# radio_fm_cd2003_tda2822.net
KiCad netlist of a schematic drawn in EAGLE
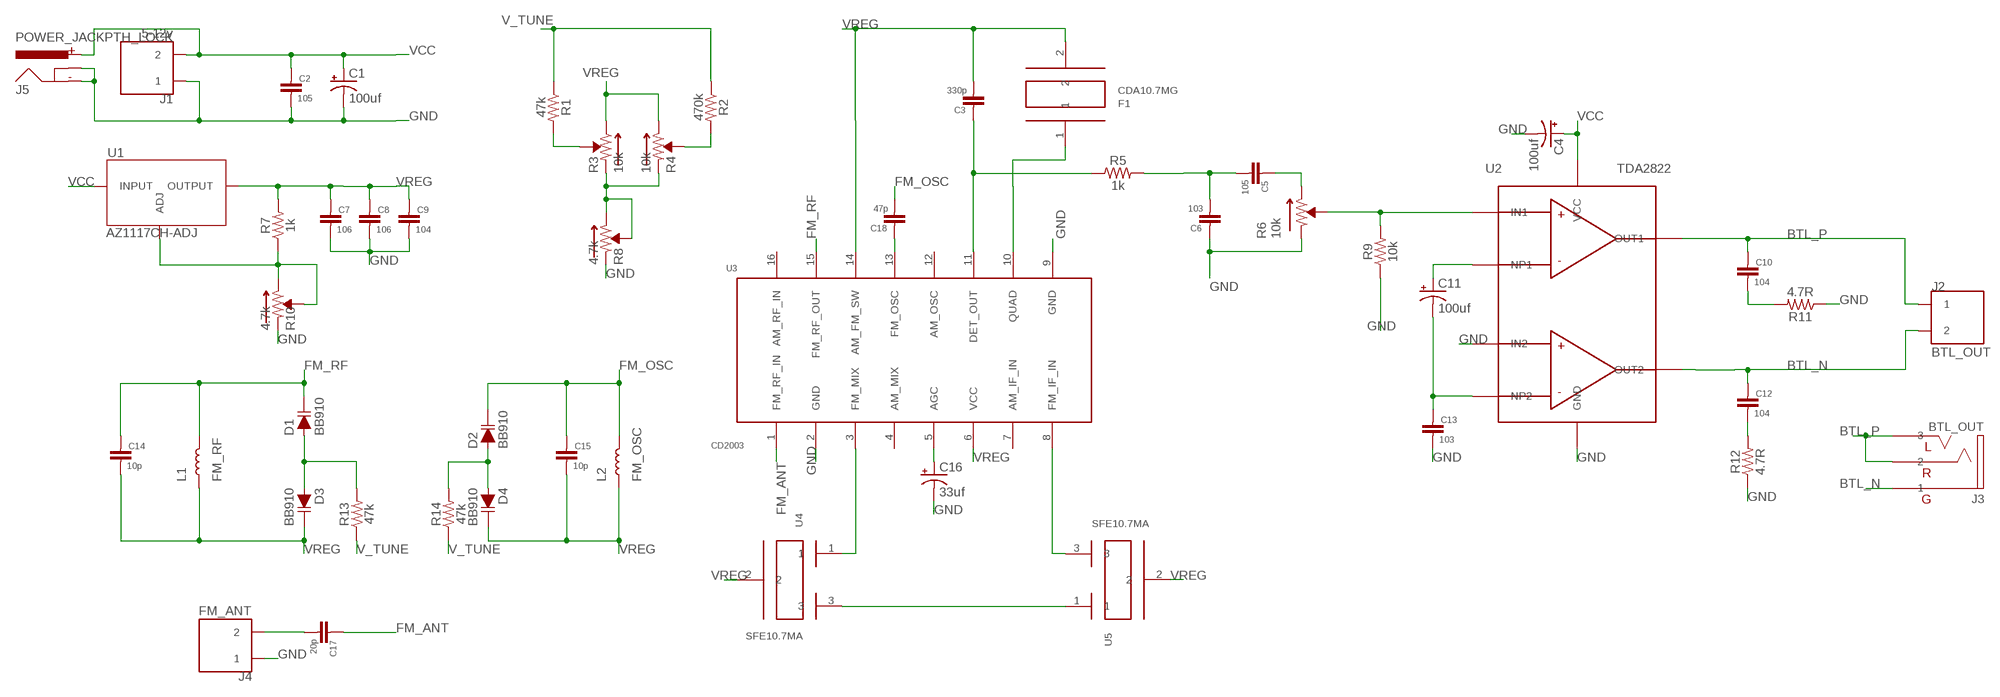
[diagram p0: schematic, sheet 1]

(export (version "E")
  (design (tool "Eeschema 10.0.6"))
  (components
    (comp (ref "C1")
      (value "100uf")
      (footprint "eagle-import:CAP_2.5MM")
      (libsource (lib "eagle-import") (part "CAP"))
    )
    (comp (ref "C2")
      (value "105")
      (footprint "eagle-import:C0603")
      (libsource (lib "eagle-import") (part "CAP_SMDC0603"))
    )
    (comp (ref "C3")
      (value "330p")
      (footprint "eagle-import:C0603")
      (libsource (lib "eagle-import") (part "CAP_SMDC0603"))
    )
    (comp (ref "C4")
      (value "100uf")
      (footprint "eagle-import:CAP_2.5MM")
      (libsource (lib "eagle-import") (part "CAP"))
    )
    (comp (ref "C5")
      (value "105")
      (footprint "eagle-import:C0603")
      (libsource (lib "eagle-import") (part "CAP_SMDC0603"))
    )
    (comp (ref "C6")
      (value "103")
      (footprint "eagle-import:C0603")
      (libsource (lib "eagle-import") (part "CAP_SMDC0603"))
    )
    (comp (ref "C7")
      (value "106")
      (footprint "eagle-import:C0603")
      (libsource (lib "eagle-import") (part "CAP_SMDC0603"))
    )
    (comp (ref "C8")
      (value "106")
      (footprint "eagle-import:C0603")
      (libsource (lib "eagle-import") (part "CAP_SMDC0603"))
    )
    (comp (ref "C9")
      (value "104")
      (footprint "eagle-import:C0603")
      (libsource (lib "eagle-import") (part "CAP_SMDC0603"))
    )
    (comp (ref "C10")
      (value "104")
      (footprint "eagle-import:C0603")
      (libsource (lib "eagle-import") (part "CAP_SMDC0603"))
    )
    (comp (ref "C11")
      (value "100uf")
      (footprint "eagle-import:CAP_2.5MM")
      (libsource (lib "eagle-import") (part "CAP"))
    )
    (comp (ref "C12")
      (value "104")
      (footprint "eagle-import:C0603")
      (libsource (lib "eagle-import") (part "CAP_SMDC0603"))
    )
    (comp (ref "C13")
      (value "103")
      (footprint "eagle-import:C0603")
      (libsource (lib "eagle-import") (part "CAP_SMDC0603"))
    )
    (comp (ref "C14")
      (value "10p")
      (footprint "eagle-import:C0603")
      (libsource (lib "eagle-import") (part "CAP_SMDC0603"))
    )
    (comp (ref "C15")
      (value "10p")
      (footprint "eagle-import:C0603")
      (libsource (lib "eagle-import") (part "CAP_SMDC0603"))
    )
    (comp (ref "C16")
      (value "33uf")
      (footprint "eagle-import:CAP_2MM")
      (libsource (lib "eagle-import") (part "CAP2MM"))
    )
    (comp (ref "C17")
      (value "20p")
      (footprint "eagle-import:C0603")
      (libsource (lib "eagle-import") (part "CAP_SMDC0603"))
    )
    (comp (ref "C18")
      (value "47p")
      (footprint "eagle-import:C0603")
      (libsource (lib "eagle-import") (part "CAP_SMDC0603"))
    )
    (comp (ref "D1")
      (value "BB910")
      (footprint "eagle-import:TO-92S")
      (libsource (lib "eagle-import") (part "VARIODE-TO92S"))
    )
    (comp (ref "D2")
      (value "BB910")
      (footprint "eagle-import:TO-92S")
      (libsource (lib "eagle-import") (part "VARIODE-TO92S"))
    )
    (comp (ref "D3")
      (value "BB910")
      (footprint "eagle-import:TO-92S")
      (libsource (lib "eagle-import") (part "VARIODE-TO92S"))
    )
    (comp (ref "D4")
      (value "BB910")
      (footprint "eagle-import:TO-92S")
      (libsource (lib "eagle-import") (part "VARIODE-TO92S"))
    )
    (comp (ref "F1")
      (value "CDA10.7MG")
      (footprint "eagle-import:CDA10.7MG")
      (libsource (lib "eagle-import") (part "CDA10.7MG"))
    )
    (comp (ref "J1")
      (value "5-12v")
      (footprint "eagle-import:2P_2.54MM")
      (libsource (lib "eagle-import") (part "2P"))
    )
    (comp (ref "J2")
      (value "BTL_OUT")
      (footprint "eagle-import:2P_5.08MM")
      (libsource (lib "eagle-import") (part "2P5.0"))
    )
    (comp (ref "J3")
      (value "BTL_OUT")
      (footprint "eagle-import:3.5MM")
      (libsource (lib "eagle-import") (part "3.5MM_PHONE"))
    )
    (comp (ref "J4")
      (value "FM_ANT")
      (footprint "eagle-import:2P_2.54MM")
      (libsource (lib "eagle-import") (part "2P"))
    )
    (comp (ref "J5")
      (value "POWER_JACKPTH_LOCK")
      (footprint "eagle-import:POWER_JACK_PTH_LOCK")
      (libsource (lib "eagle-import") (part "POWER_JACKPTH_LOCK"))
    )
    (comp (ref "L1")
      (value "FM_RF")
      (footprint "eagle-import:VLU0810")
      (libsource (lib "eagle-import") (part "INDUCTOR_PTH"))
    )
    (comp (ref "L2")
      (value "FM_OSC")
      (footprint "eagle-import:VLU0810")
      (libsource (lib "eagle-import") (part "INDUCTOR_PTH"))
    )
    (comp (ref "R1")
      (value "47k")
      (footprint "eagle-import:R0603")
      (libsource (lib "eagle-import") (part "RESISTOR_SMDR0603"))
    )
    (comp (ref "R2")
      (value "470k")
      (footprint "eagle-import:R0603")
      (libsource (lib "eagle-import") (part "RESISTOR_SMDR0603"))
    )
    (comp (ref "R3")
      (value "10k")
      (footprint "eagle-import:3362P")
      (libsource (lib "eagle-import") (part "RES_ADJ"))
    )
    (comp (ref "R4")
      (value "10k")
      (footprint "eagle-import:3362P")
      (libsource (lib "eagle-import") (part "RES_ADJ"))
    )
    (comp (ref "R5")
      (value "1k")
      (footprint "eagle-import:R0603")
      (libsource (lib "eagle-import") (part "RESISTOR_SMDR0603"))
    )
    (comp (ref "R6")
      (value "10k")
      (footprint "eagle-import:3362P")
      (libsource (lib "eagle-import") (part "RES_ADJ"))
    )
    (comp (ref "R7")
      (value "1k")
      (footprint "eagle-import:R0603")
      (libsource (lib "eagle-import") (part "RESISTOR_SMDR0603"))
    )
    (comp (ref "R8")
      (value "4.7k")
      (footprint "eagle-import:3362P")
      (libsource (lib "eagle-import") (part "RES_ADJ"))
    )
    (comp (ref "R9")
      (value "10k")
      (footprint "eagle-import:R0603")
      (libsource (lib "eagle-import") (part "RESISTOR_SMDR0603"))
    )
    (comp (ref "R10")
      (value "4.7k")
      (footprint "eagle-import:3362P")
      (libsource (lib "eagle-import") (part "RES_ADJ"))
    )
    (comp (ref "R11")
      (value "4.7R")
      (footprint "eagle-import:R0603")
      (libsource (lib "eagle-import") (part "RESISTOR_SMDR0603"))
    )
    (comp (ref "R12")
      (value "4.7R")
      (footprint "eagle-import:R0603")
      (libsource (lib "eagle-import") (part "RESISTOR_SMDR0603"))
    )
    (comp (ref "R13")
      (value "47k")
      (footprint "eagle-import:R0603")
      (libsource (lib "eagle-import") (part "RESISTOR_SMDR0603"))
    )
    (comp (ref "R14")
      (value "47k")
      (footprint "eagle-import:R0603")
      (libsource (lib "eagle-import") (part "RESISTOR_SMDR0603"))
    )
    (comp (ref "U1")
      (value "AZ1117CH-ADJ")
      (footprint "eagle-import:SOT-223")
      (libsource (lib "eagle-import") (part "AZ1117CH-ADJ"))
    )
    (comp (ref "U2")
      (value "TDA2822")
      (footprint "eagle-import:DIP8")
      (libsource (lib "eagle-import") (part "TDA2822-DIP8"))
    )
    (comp (ref "U3")
      (value "CD2003")
      (footprint "eagle-import:DIP16")
      (libsource (lib "eagle-import") (part "TA2003"))
    )
    (comp (ref "U4")
      (value "SFE10.7MA")
      (footprint "eagle-import:SFE10.7MA")
      (libsource (lib "eagle-import") (part "SFE10.7MA"))
    )
    (comp (ref "U5")
      (value "SFE10.7MA")
      (footprint "eagle-import:SFE10.7MA")
      (libsource (lib "eagle-import") (part "SFE10.7MA"))
    )
  )
  (nets
    (net (code "1") (name "/BTL_N") (class "Default")
      (node (ref "C12") (pin "1") (pinfunction "1_1") (pintype "passive"))
      (node (ref "J2") (pin "N") (pinfunction "2_N") (pintype "bidirectional"))
      (node (ref "J3") (pin "P$1") (pinfunction "1_P$1") (pintype "bidirectional"))
      (node (ref "U2") (pin "P$3") (pinfunction "OUT2_P$3") (pintype "bidirectional"))
    )
    (net (code "2") (name "/BTL_P") (class "Default")
      (node (ref "C10") (pin "1") (pinfunction "1_1") (pintype "passive"))
      (node (ref "J2") (pin "L") (pinfunction "1_L") (pintype "bidirectional"))
      (node (ref "J3") (pin "P$2") (pinfunction "2_P$2") (pintype "bidirectional"))
      (node (ref "J3") (pin "P$3") (pinfunction "3_P$3") (pintype "bidirectional"))
      (node (ref "U2") (pin "P$1") (pinfunction "OUT1_P$1") (pintype "bidirectional"))
    )
    (net (code "3") (name "/FM_ANT") (class "Default")
      (node (ref "C17") (pin "1") (pinfunction "1_1") (pintype "passive"))
      (node (ref "U3") (pin "1") (pinfunction "FM_RF_IN_1") (pintype "bidirectional"))
    )
    (net (code "4") (name "/FM_OSC") (class "Default")
      (node (ref "C15") (pin "1") (pinfunction "1_1") (pintype "passive"))
      (node (ref "C18") (pin "2") (pinfunction "2_2") (pintype "passive"))
      (node (ref "D2") (pin "2") (pinfunction "C_2") (pintype "passive"))
      (node (ref "L2") (pin "-") (pinfunction "2_-") (pintype "passive"))
    )
    (net (code "5") (name "/FM_RF") (class "Default")
      (node (ref "C14") (pin "1") (pinfunction "1_1") (pintype "passive"))
      (node (ref "D1") (pin "2") (pinfunction "C_2") (pintype "passive"))
      (node (ref "L1") (pin "-") (pinfunction "2_-") (pintype "passive"))
      (node (ref "U3") (pin "15") (pinfunction "FM_RF_OUT_15") (pintype "bidirectional"))
    )
    (net (code "6") (name "/GND") (class "Default")
      (node (ref "C1") (pin "-") (pinfunction "-_-") (pintype "passive"))
      (node (ref "C13") (pin "2") (pinfunction "2_2") (pintype "passive"))
      (node (ref "C16") (pin "-") (pinfunction "-_-") (pintype "passive"))
      (node (ref "C2") (pin "2") (pinfunction "2_2") (pintype "passive"))
      (node (ref "C4") (pin "-") (pinfunction "-_-") (pintype "passive"))
      (node (ref "C6") (pin "1") (pinfunction "1_1") (pintype "passive"))
      (node (ref "C7") (pin "2") (pinfunction "2_2") (pintype "passive"))
      (node (ref "C8") (pin "2") (pinfunction "2_2") (pintype "passive"))
      (node (ref "C9") (pin "2") (pinfunction "2_2") (pintype "passive"))
      (node (ref "J1") (pin "1") (pinfunction "1_1") (pintype "bidirectional"))
      (node (ref "J4") (pin "1") (pinfunction "1_1") (pintype "bidirectional"))
      (node (ref "J5") (pin "GND") (pinfunction "GND_GND") (pintype "bidirectional"))
      (node (ref "J5") (pin "GNDBREAK") (pinfunction "GNDBREAK_GNDBREAK") (pintype "bidirectional"))
      (node (ref "R10") (pin "P$1") (pinfunction "1_P$1") (pintype "passive"))
      (node (ref "R11") (pin "1") (pinfunction "1_1") (pintype "passive"))
      (node (ref "R12") (pin "1") (pinfunction "1_1") (pintype "passive"))
      (node (ref "R6") (pin "P$1") (pinfunction "1_P$1") (pintype "passive"))
      (node (ref "R8") (pin "P$1") (pinfunction "1_P$1") (pintype "passive"))
      (node (ref "R9") (pin "1") (pinfunction "1_1") (pintype "passive"))
      (node (ref "U2") (pin "P$4") (pinfunction "GND_P$4") (pintype "bidirectional"))
      (node (ref "U2") (pin "P$6") (pinfunction "IN2_P$6") (pintype "bidirectional"))
      (node (ref "U3") (pin "2") (pinfunction "GND_2") (pintype "bidirectional"))
      (node (ref "U3") (pin "9") (pinfunction "GND_9") (pintype "bidirectional"))
    )
    (net (code "7") (name "/VCC") (class "Default")
      (node (ref "C1") (pin "+") (pinfunction "+_+") (pintype "passive"))
      (node (ref "C2") (pin "1") (pinfunction "1_1") (pintype "passive"))
      (node (ref "C4") (pin "+") (pinfunction "+_+") (pintype "passive"))
      (node (ref "J1") (pin "2") (pinfunction "2_2") (pintype "bidirectional"))
      (node (ref "J5") (pin "PWR") (pinfunction "PWR_PWR") (pintype "bidirectional"))
      (node (ref "U1") (pin "3") (pinfunction "INPUT_3") (pintype "bidirectional"))
      (node (ref "U2") (pin "P$2") (pinfunction "VCC_P$2") (pintype "bidirectional"))
    )
    (net (code "8") (name "/VREG") (class "Default")
      (node (ref "C14") (pin "2") (pinfunction "2_2") (pintype "passive"))
      (node (ref "C15") (pin "2") (pinfunction "2_2") (pintype "passive"))
      (node (ref "C3") (pin "2") (pinfunction "2_2") (pintype "passive"))
      (node (ref "C7") (pin "1") (pinfunction "1_1") (pintype "passive"))
      (node (ref "C8") (pin "1") (pinfunction "1_1") (pintype "passive"))
      (node (ref "C9") (pin "1") (pinfunction "1_1") (pintype "passive"))
      (node (ref "D3") (pin "2") (pinfunction "C_2") (pintype "passive"))
      (node (ref "D4") (pin "2") (pinfunction "C_2") (pintype "passive"))
      (node (ref "F1") (pin "2") (pinfunction "2_2") (pintype "bidirectional"))
      (node (ref "L1") (pin "+") (pinfunction "1_+") (pintype "passive"))
      (node (ref "L2") (pin "+") (pinfunction "1_+") (pintype "passive"))
      (node (ref "R3") (pin "P$3") (pinfunction "3_P$3") (pintype "passive"))
      (node (ref "R4") (pin "P$3") (pinfunction "3_P$3") (pintype "passive"))
      (node (ref "R7") (pin "2") (pinfunction "2_2") (pintype "passive"))
      (node (ref "U1") (pin "2") (pinfunction "OUTPUT_2") (pintype "bidirectional"))
      (node (ref "U3") (pin "14") (pinfunction "AM_FM_SW_14") (pintype "bidirectional"))
      (node (ref "U3") (pin "6") (pinfunction "VCC_6") (pintype "bidirectional"))
      (node (ref "U4") (pin "2") (pinfunction "2_2") (pintype "bidirectional"))
      (node (ref "U5") (pin "2") (pinfunction "2_2") (pintype "bidirectional"))
    )
    (net (code "9") (name "/V_TUNE") (class "Default")
      (node (ref "R1") (pin "1") (pinfunction "1_1") (pintype "passive"))
      (node (ref "R13") (pin "1") (pinfunction "1_1") (pintype "passive"))
      (node (ref "R14") (pin "1") (pinfunction "1_1") (pintype "passive"))
      (node (ref "R2") (pin "1") (pinfunction "1_1") (pintype "passive"))
    )
    (net (code "10") (name "Net-(C5-Pad2)") (class "Default")
      (node (ref "C5") (pin "2") (pinfunction "2_2") (pintype "passive"))
      (node (ref "C6") (pin "2") (pinfunction "2_2") (pintype "passive"))
      (node (ref "R5") (pin "2") (pinfunction "2_2") (pintype "passive"))
    )
    (net (code "11") (name "Net-(C10-Pad2)") (class "Default")
      (node (ref "C10") (pin "2") (pinfunction "2_2") (pintype "passive"))
      (node (ref "R11") (pin "2") (pinfunction "2_2") (pintype "passive"))
    )
    (net (code "12") (name "Net-(C12-Pad2)") (class "Default")
      (node (ref "C12") (pin "2") (pinfunction "2_2") (pintype "passive"))
      (node (ref "R12") (pin "2") (pinfunction "2_2") (pintype "passive"))
    )
    (net (code "13") (name "Net-(C17-Pad2)") (class "Default")
      (node (ref "C17") (pin "2") (pinfunction "2_2") (pintype "passive"))
      (node (ref "J4") (pin "2") (pinfunction "2_2") (pintype "bidirectional"))
    )
    (net (code "14") (name "Net-(D1-A)") (class "Default")
      (node (ref "D1") (pin "1") (pinfunction "A_1") (pintype "passive"))
      (node (ref "D3") (pin "1") (pinfunction "A_1") (pintype "passive"))
      (node (ref "R13") (pin "2") (pinfunction "2_2") (pintype "passive"))
    )
    (net (code "15") (name "Net-(D2-A)") (class "Default")
      (node (ref "D2") (pin "1") (pinfunction "A_1") (pintype "passive"))
      (node (ref "D4") (pin "1") (pinfunction "A_1") (pintype "passive"))
      (node (ref "R14") (pin "2") (pinfunction "2_2") (pintype "passive"))
    )
    (net (code "16") (name "Net-(R3-1)") (class "Default")
      (node (ref "R3") (pin "P$1") (pinfunction "1_P$1") (pintype "passive"))
      (node (ref "R4") (pin "P$1") (pinfunction "1_P$1") (pintype "passive"))
      (node (ref "R8") (pin "P$2") (pinfunction "2_P$2") (pintype "passive"))
      (node (ref "R8") (pin "P$3") (pinfunction "3_P$3") (pintype "passive"))
    )
    (net (code "17") (name "Net-(R3-2)") (class "Default")
      (node (ref "R1") (pin "2") (pinfunction "2_2") (pintype "passive"))
      (node (ref "R3") (pin "P$2") (pinfunction "2_P$2") (pintype "passive"))
    )
    (net (code "18") (name "Net-(R4-2)") (class "Default")
      (node (ref "R2") (pin "2") (pinfunction "2_2") (pintype "passive"))
      (node (ref "R4") (pin "P$2") (pinfunction "2_P$2") (pintype "passive"))
    )
    (net (code "19") (name "Net-(R6-2)") (class "Default")
      (node (ref "R6") (pin "P$2") (pinfunction "2_P$2") (pintype "passive"))
      (node (ref "R9") (pin "2") (pinfunction "2_2") (pintype "passive"))
      (node (ref "U2") (pin "P$7") (pinfunction "IN1_P$7") (pintype "bidirectional"))
    )
    (net (code "20") (name "Net-(R6-3)") (class "Default")
      (node (ref "C5") (pin "1") (pinfunction "1_1") (pintype "passive"))
      (node (ref "R6") (pin "P$3") (pinfunction "3_P$3") (pintype "passive"))
    )
    (net (code "21") (name "Net-(R10-2)") (class "Default")
      (node (ref "R10") (pin "P$2") (pinfunction "2_P$2") (pintype "passive"))
      (node (ref "R10") (pin "P$3") (pinfunction "3_P$3") (pintype "passive"))
      (node (ref "R7") (pin "1") (pinfunction "1_1") (pintype "passive"))
      (node (ref "U1") (pin "1") (pinfunction "ADJ_1") (pintype "bidirectional"))
    )
    (net (code "22") (name "Net-(U2-NP1)") (class "Default")
      (node (ref "C11") (pin "+") (pinfunction "+_+") (pintype "passive"))
      (node (ref "U2") (pin "P$8") (pinfunction "NP1_P$8") (pintype "bidirectional"))
    )
    (net (code "23") (name "Net-(U2-NP2)") (class "Default")
      (node (ref "C11") (pin "-") (pinfunction "-_-") (pintype "passive"))
      (node (ref "C13") (pin "1") (pinfunction "1_1") (pintype "passive"))
      (node (ref "U2") (pin "P$5") (pinfunction "NP2_P$5") (pintype "bidirectional"))
    )
    (net (code "24") (name "Net-(U3-AGC)") (class "Default")
      (node (ref "C16") (pin "+") (pinfunction "+_+") (pintype "passive"))
      (node (ref "U3") (pin "5") (pinfunction "AGC_5") (pintype "bidirectional"))
    )
    (net (code "25") (name "Net-(U3-DET_OUT)") (class "Default")
      (node (ref "C3") (pin "1") (pinfunction "1_1") (pintype "passive"))
      (node (ref "R5") (pin "1") (pinfunction "1_1") (pintype "passive"))
      (node (ref "U3") (pin "11") (pinfunction "DET_OUT_11") (pintype "bidirectional"))
    )
    (net (code "26") (name "Net-(U3-FM_IF_IN)") (class "Default")
      (node (ref "U3") (pin "8") (pinfunction "FM_IF_IN_8") (pintype "bidirectional"))
      (node (ref "U5") (pin "3") (pinfunction "3_3") (pintype "bidirectional"))
    )
    (net (code "27") (name "Net-(U3-FM_MIX)") (class "Default")
      (node (ref "U3") (pin "3") (pinfunction "FM_MIX_3") (pintype "bidirectional"))
      (node (ref "U4") (pin "1") (pinfunction "1_1") (pintype "bidirectional"))
    )
    (net (code "28") (name "Net-(U3-FM_OSC)") (class "Default")
      (node (ref "C18") (pin "1") (pinfunction "1_1") (pintype "passive"))
      (node (ref "U3") (pin "13") (pinfunction "FM_OSC_13") (pintype "bidirectional"))
    )
    (net (code "29") (name "Net-(U3-QUAD)") (class "Default")
      (node (ref "F1") (pin "1") (pinfunction "1_1") (pintype "bidirectional"))
      (node (ref "U3") (pin "10") (pinfunction "QUAD_10") (pintype "bidirectional"))
    )
    (net (code "30") (name "Net-(U4-Pad3)") (class "Default")
      (node (ref "U4") (pin "3") (pinfunction "3_3") (pintype "bidirectional"))
      (node (ref "U5") (pin "1") (pinfunction "1_1") (pintype "bidirectional"))
    )
    (net (code "31") (name "unconnected-(U3-AM_IF_IN-Pad7)") (class "Default")
      (node (ref "U3") (pin "7") (pinfunction "AM_IF_IN_7") (pintype "bidirectional"))
    )
    (net (code "32") (name "unconnected-(U3-AM_MIX-Pad4)") (class "Default")
      (node (ref "U3") (pin "4") (pinfunction "AM_MIX_4") (pintype "bidirectional"))
    )
    (net (code "33") (name "unconnected-(U3-AM_OSC-Pad12)") (class "Default")
      (node (ref "U3") (pin "12") (pinfunction "AM_OSC_12") (pintype "bidirectional"))
    )
    (net (code "34") (name "unconnected-(U3-AM_RF_IN-Pad16)") (class "Default")
      (node (ref "U3") (pin "16") (pinfunction "AM_RF_IN_16") (pintype "bidirectional"))
    )
  )
)
